# power.net
KiCad netlist of a schematic drawn in Altium Designer
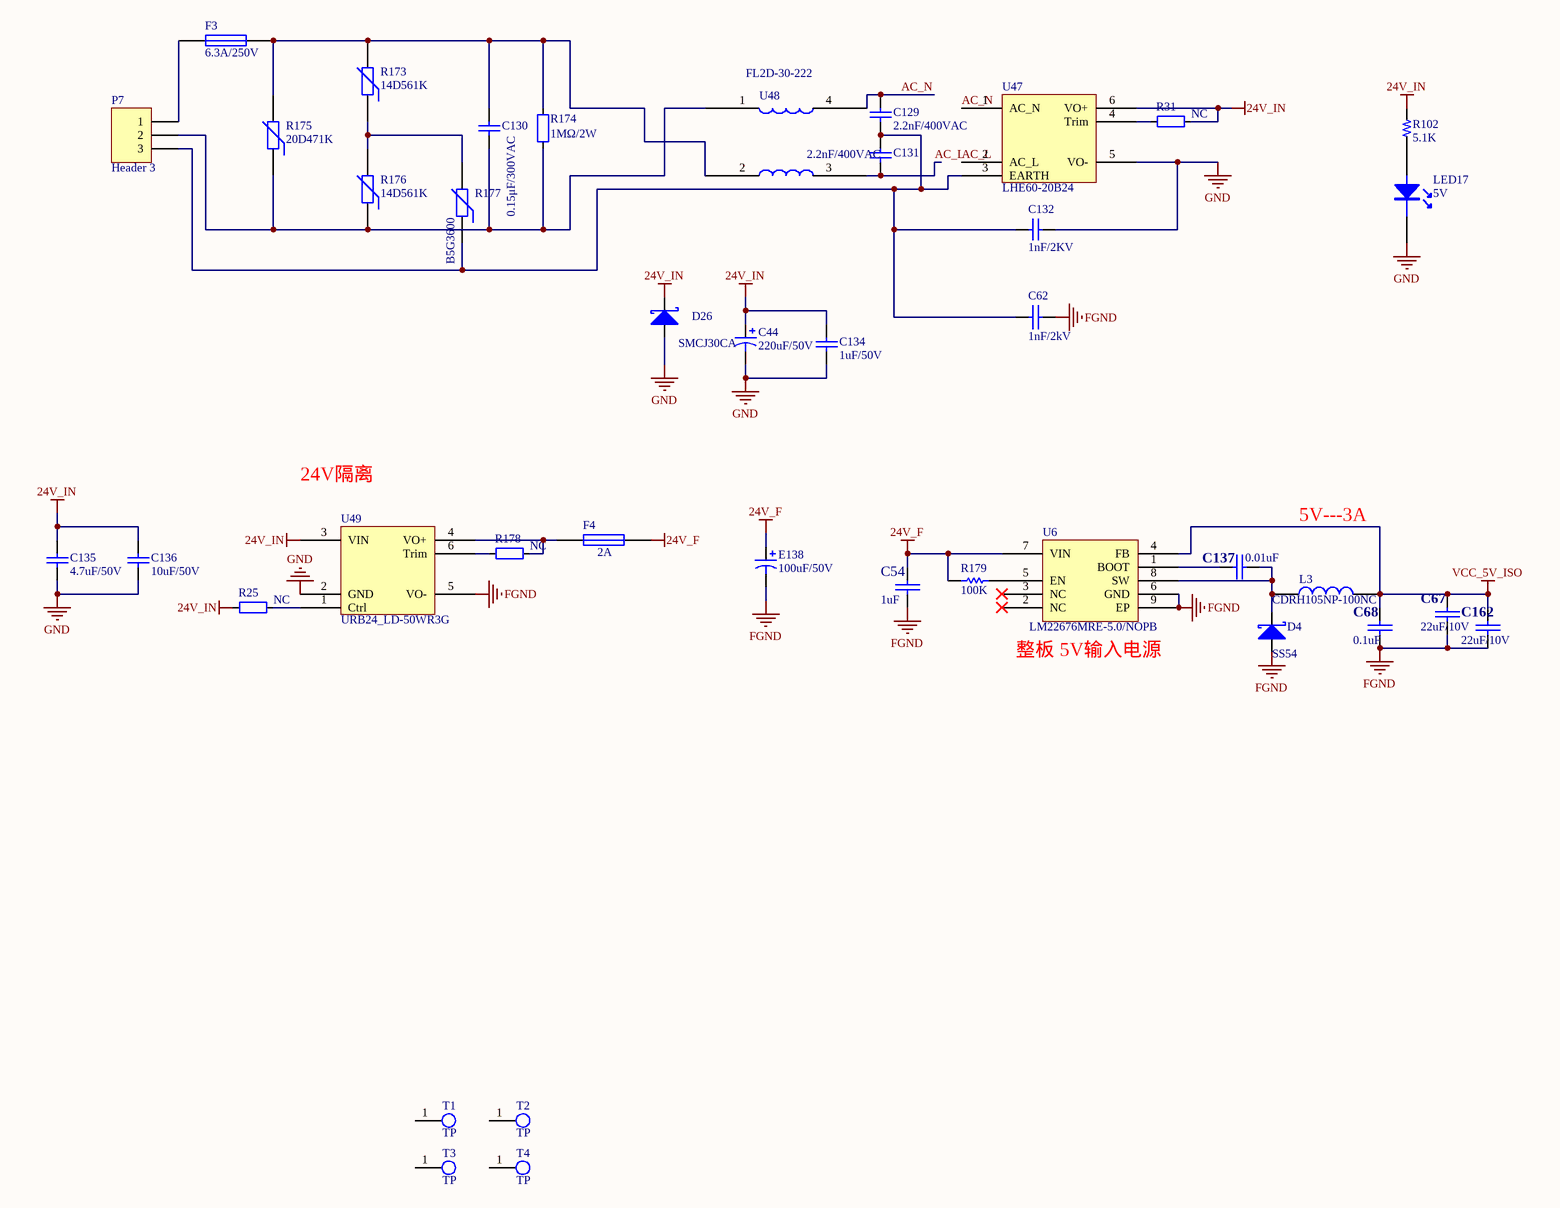
[diagram p0: power.SchDoc]

(export (version "E")
  (design (tool "Eeschema 10.0.6"))
  (components
    (comp (ref "C44")
      (value "220uF/50V")
      (footprint "Φ10×10")
      (description "Polarized Capacitor (Radial)")
      (fields (field (name "PUBLISHER") "Altium Limited"))
      (libsource (lib "Miscellaneous Devices") (part "Cap Pol1"))
    )
    (comp (ref "C54")
      (value "1uF")
      (footprint "0603C")
      (description "Capacitor")
      (libsource (lib "*") (part "CAP"))
    )
    (comp (ref "C62")
      (value "1nF/2kV")
      (footprint "1206C")
      (description "Capacitor")
      (libsource (lib "*") (part "CAP"))
    )
    (comp (ref "C67")
      (value "22uF/10V")
      (footprint "1210C")
      (description "Capacitor")
      (libsource (lib "*") (part "CAP"))
    )
    (comp (ref "C68")
      (value "0.1uF")
      (footprint "0603C")
      (description "Capacitor")
      (libsource (lib "*") (part "CAP"))
    )
    (comp (ref "C129")
      (value "2.2nF/400VAC")
      (footprint "15x18")
      (description "Capacitor")
      (fields (field (name "PUBLISHER") "Altium Limited"))
      (libsource (lib "Miscellaneous Devices") (part "Cap"))
    )
    (comp (ref "C130")
      (value "0.15μF/300VAC")
      (footprint "15x18")
      (description "Capacitor")
      (fields (field (name "PUBLISHER") "Altium Limited"))
      (libsource (lib "Miscellaneous Devices") (part "Cap"))
    )
    (comp (ref "C131")
      (value "2.2nF/400VAC")
      (footprint "15x18")
      (description "Capacitor")
      (fields (field (name "PUBLISHER") "Altium Limited"))
      (libsource (lib "Miscellaneous Devices") (part "Cap"))
    )
    (comp (ref "C132")
      (value "1nF/2KV")
      (footprint "1206C")
      (description "Capacitor")
      (fields (field (name "PUBLISHER") "Altium Limited"))
      (libsource (lib "Miscellaneous Devices") (part "Cap"))
    )
    (comp (ref "C134")
      (value "1uF/50V")
      (footprint "1210C")
      (description "Capacitor")
      (fields (field (name "PUBLISHER") "Altium Limited"))
      (libsource (lib "Miscellaneous Devices") (part "Cap"))
    )
    (comp (ref "C135")
      (value "4.7uF/50V")
      (footprint "1210C")
      (description "Capacitor")
      (fields (field (name "PUBLISHER") "Altium Limited"))
      (libsource (lib "Miscellaneous Devices") (part "Cap"))
    )
    (comp (ref "C136")
      (value "10uF/50V")
      (footprint "1210C")
      (description "Capacitor")
      (fields (field (name "PUBLISHER") "Altium Limited"))
      (libsource (lib "Miscellaneous Devices") (part "Cap"))
    )
    (comp (ref "C137")
      (value "0.01uF")
      (footprint "0603C")
      (description "Capacitor")
      (libsource (lib "*") (part "CAP"))
    )
    (comp (ref "C162")
      (value "22uF/10V")
      (footprint "1210C")
      (description "Capacitor")
      (libsource (lib "*") (part "CAP"))
    )
    (comp (ref "D4")
      (value "SS54")
      (footprint "SMC")
      (description "Schottky Diode")
      (libsource (lib "*") (part "DIODE S"))
    )
    (comp (ref "D26")
      (value "SMCJ30CA")
      (footprint "SMC")
      (description "Schottky Diode")
      (libsource (lib "*") (part "DIODE S"))
    )
    (comp (ref "E138")
      (value "100uF/50V")
      (footprint "Φ10×10")
      (description "Polarized Capacitor (Radial)")
      (fields (field (name "PUBLISHER") "Altium Limited"))
      (libsource (lib "Miscellaneous Devices") (part "Cap Pol1"))
    )
    (comp (ref "F3")
      (value "6.3A/250V")
      (footprint "可视开关电源保险丝座")
      (description "Fuse")
      (fields (field (name "PUBLISHER") "Altium Limited"))
      (libsource (lib "Miscellaneous Devices") (part "Fuse 1"))
    )
    (comp (ref "F4")
      (value "2A")
      (footprint "1812-F")
      (description "Fuse")
      (fields (field (name "PUBLISHER") "Altium Limited"))
      (libsource (lib "Miscellaneous Devices") (part "Fuse 1"))
    )
    (comp (ref "L3") (value "CDRH105NP-100NC") (footprint "CDRH105") (libsource (lib "*") (part "INDUCTOR")))
    (comp (ref "LED17") (value "5V") (footprint "0603LED") (libsource (lib "*") (part "LED")))
    (comp (ref "P7")
      (value "Header 3")
      (footprint "KF128V-3P")
      (description "Header, 3-Pin")
      (fields (field (name "PUBLISHER") "Altium Limited"))
      (libsource (lib "Miscellaneous Connectors") (part "Header 3"))
    )
    (comp (ref "R25") (value "NC") (footprint "0603r") (libsource (lib "RC_M_D_00") (part "RES0603")))
    (comp (ref "R31") (value "NC") (footprint "0603r") (libsource (lib "RC_M_D_00") (part "RES0603")))
    (comp (ref "R102")
      (value "5.1K")
      (footprint "0603R")
      (description "R")
      (libsource (lib "JRJ_1") (part "R"))
    )
    (comp (ref "R173")
      (value "14D561K")
      (footprint "14D561K")
      (description "Varistor (Voltage-Sensitive Resistor)")
      (fields (field (name "PUBLISHER") "Altium Limited"))
      (libsource (lib "Miscellaneous Devices") (part "Res Varistor"))
    )
    (comp (ref "R174") (value "1MΩ/2W") (footprint "5x15.5") (libsource (lib "RC_M_D_00") (part "RES0603")))
    (comp (ref "R175")
      (value "20D471K")
      (footprint "20D471K")
      (description "Varistor (Voltage-Sensitive Resistor)")
      (fields (field (name "PUBLISHER") "Altium Limited"))
      (libsource (lib "Miscellaneous Devices") (part "Res Varistor"))
    )
    (comp (ref "R176")
      (value "14D561K")
      (footprint "14D561K")
      (description "Varistor (Voltage-Sensitive Resistor)")
      (fields (field (name "PUBLISHER") "Altium Limited"))
      (libsource (lib "Miscellaneous Devices") (part "Res Varistor"))
    )
    (comp (ref "R177")
      (value "B5G3600")
      (footprint "B5G3600")
      (description "Varistor (Voltage-Sensitive Resistor)")
      (fields (field (name "PUBLISHER") "Altium Limited"))
      (libsource (lib "Miscellaneous Devices") (part "Res Varistor"))
    )
    (comp (ref "R178") (value "NC") (footprint "0603r") (libsource (lib "RC_M_D_00") (part "RES0603")))
    (comp (ref "R179")
      (value "100K")
      (footprint "0603R")
      (description "Resistor")
      (fields (field (name "PUBLISHER") "Altium Limited"))
      (libsource (lib "Miscellaneous Devices") (part "Res1"))
    )
    (comp (ref "T1") (value "TP") (footprint "m2.5") (libsource (lib "Schlib_20110825") (part "TP")))
    (comp (ref "T2") (value "TP") (footprint "m2.5") (libsource (lib "Schlib_20110825") (part "TP")))
    (comp (ref "T3") (value "TP") (footprint "m2.5") (libsource (lib "Schlib_20110825") (part "TP")))
    (comp (ref "T4") (value "TP") (footprint "m2.5") (libsource (lib "Schlib_20110825") (part "TP")))
    (comp (ref "U6")
      (value "LM22676MRE-5.0/NOPB")
      (footprint "SOP127P600X168_HS-8N")
      (libsource (lib "Schlib1") (part "LM22676MR-5.0"))
    )
    (comp (ref "U47")
      (value "LHE60-20B24")
      (footprint "LHE60-20B24")
      (libsource (lib "Schlib1") (part "LHE60-20B24"))
    )
    (comp (ref "U48")
      (value "FL2D-30-222")
      (footprint "TY-100P")
      (description "PCB mounting filters")
      (libsource (lib "power") (part "TY-100P"))
    )
    (comp (ref "U49")
      (value "URB24_LD-50WR3G")
      (footprint "URB24_LD-50WR3G")
      (libsource (lib "Schlib1") (part "URB24_LD-50WR3G"))
    )
  )
  (nets
    (net (code "1") (name "/AC_L") (class "Default")
      (node (ref "C131") (pin "1") (pinfunction "1_1") (pintype "passive"))
      (node (ref "U47") (pin "2") (pinfunction "AC_L_2") (pintype "passive"))
      (node (ref "U48") (pin "3") (pintype "passive"))
    )
    (net (code "2") (name "/AC_N") (class "Default")
      (node (ref "C129") (pin "2") (pinfunction "2_2") (pintype "passive"))
      (node (ref "U47") (pin "1") (pinfunction "AC_N_1") (pintype "passive"))
      (node (ref "U48") (pin "4") (pinfunction "L_4") (pintype "passive"))
    )
    (net (code "3") (name "24V_F") (class "Default")
      (node (ref "C54") (pin "2") (pinfunction "2_2") (pintype "passive"))
      (node (ref "E138") (pin "1") (pinfunction "1_1") (pintype "passive"))
      (node (ref "F4") (pin "2") (pinfunction "2_2") (pintype "passive"))
      (node (ref "R179") (pin "2") (pinfunction "2_2") (pintype "passive"))
      (node (ref "U6") (pin "7") (pinfunction "VIN_7") (pintype "passive"))
    )
    (net (code "4") (name "24V_IN") (class "Default")
      (node (ref "C134") (pin "2") (pinfunction "2_2") (pintype "passive"))
      (node (ref "C135") (pin "2") (pinfunction "2_2") (pintype "passive"))
      (node (ref "C136") (pin "2") (pinfunction "2_2") (pintype "passive"))
      (node (ref "C44") (pin "1") (pinfunction "1_1") (pintype "passive"))
      (node (ref "D26") (pin "2") (pinfunction "K_2") (pintype "passive"))
      (node (ref "R102") (pin "2") (pintype "passive"))
      (node (ref "R25") (pin "1") (pinfunction "1_1") (pintype "passive"))
      (node (ref "R31") (pin "2") (pinfunction "2_2") (pintype "passive"))
      (node (ref "U47") (pin "6") (pinfunction "VO+_6") (pintype "passive"))
      (node (ref "U49") (pin "3") (pinfunction "VIN_3") (pintype "passive"))
    )
    (net (code "5") (name "FGND") (class "Default")
      (node (ref "C162") (pin "2") (pinfunction "2_2") (pintype "passive"))
      (node (ref "C54") (pin "1") (pinfunction "1_1") (pintype "passive"))
      (node (ref "C62") (pin "1") (pinfunction "1_1") (pintype "passive"))
      (node (ref "C67") (pin "2") (pinfunction "2_2") (pintype "passive"))
      (node (ref "C68") (pin "2") (pinfunction "2_2") (pintype "passive"))
      (node (ref "D4") (pin "1") (pinfunction "A_1") (pintype "passive"))
      (node (ref "E138") (pin "2") (pinfunction "2_2") (pintype "passive"))
      (node (ref "U49") (pin "5") (pinfunction "VO-_5") (pintype "passive"))
      (node (ref "U6") (pin "6") (pinfunction "GND_6") (pintype "passive"))
      (node (ref "U6") (pin "9") (pinfunction "EP_9") (pintype "passive"))
    )
    (net (code "6") (name "GND") (class "Default")
      (node (ref "C132") (pin "1") (pinfunction "1_1") (pintype "passive"))
      (node (ref "C134") (pin "1") (pinfunction "1_1") (pintype "passive"))
      (node (ref "C135") (pin "1") (pinfunction "1_1") (pintype "passive"))
      (node (ref "C136") (pin "1") (pinfunction "1_1") (pintype "passive"))
      (node (ref "C44") (pin "2") (pinfunction "2_2") (pintype "passive"))
      (node (ref "D26") (pin "1") (pinfunction "A_1") (pintype "passive"))
      (node (ref "LED17") (pin "2") (pinfunction "2_2") (pintype "passive"))
      (node (ref "U47") (pin "5") (pinfunction "VO-_5") (pintype "passive"))
      (node (ref "U49") (pin "2") (pinfunction "GND_2") (pintype "passive"))
    )
    (net (code "7") (name "Net-(C130-Pad1)") (class "Default")
      (node (ref "C130") (pin "1") (pinfunction "1_1") (pintype "passive"))
      (node (ref "P7") (pin "2") (pinfunction "2_2") (pintype "passive"))
      (node (ref "R174") (pin "2") (pinfunction "2_2") (pintype "passive"))
      (node (ref "R175") (pin "1") (pinfunction "1_1") (pintype "passive"))
      (node (ref "R176") (pin "1") (pinfunction "1_1") (pintype "passive"))
      (node (ref "U48") (pin "1") (pinfunction "L_1") (pintype "passive"))
    )
    (net (code "8") (name "Net-(C130-Pad2)") (class "Default")
      (node (ref "C130") (pin "2") (pinfunction "2_2") (pintype "passive"))
      (node (ref "F3") (pin "2") (pinfunction "2_2") (pintype "passive"))
      (node (ref "R173") (pin "2") (pinfunction "2_2") (pintype "passive"))
      (node (ref "R174") (pin "1") (pinfunction "1_1") (pintype "passive"))
      (node (ref "R175") (pin "2") (pinfunction "2_2") (pintype "passive"))
      (node (ref "U48") (pin "2") (pinfunction "L_2") (pintype "passive"))
    )
    (net (code "9") (name "Net-(D4-K)") (class "Default")
      (node (ref "C137") (pin "1") (pinfunction "1_1") (pintype "passive"))
      (node (ref "D4") (pin "2") (pinfunction "K_2") (pintype "passive"))
      (node (ref "L3") (pin "1") (pinfunction "1_1") (pintype "passive"))
      (node (ref "U6") (pin "8") (pinfunction "SW_8") (pintype "passive"))
    )
    (net (code "10") (name "Net-(F3-Pad1)") (class "Default")
      (node (ref "F3") (pin "1") (pinfunction "1_1") (pintype "passive"))
      (node (ref "P7") (pin "1") (pinfunction "1_1") (pintype "passive"))
    )
    (net (code "11") (name "Net-(LED17-Pad1)") (class "Default")
      (node (ref "LED17") (pin "1") (pinfunction "1_1") (pintype "passive"))
      (node (ref "R102") (pin "1") (pintype "passive"))
    )
    (net (code "12") (name "Net-(R173-Pad1)") (class "Default")
      (node (ref "R173") (pin "1") (pinfunction "1_1") (pintype "passive"))
      (node (ref "R176") (pin "2") (pinfunction "2_2") (pintype "passive"))
      (node (ref "R177") (pin "2") (pinfunction "2_2") (pintype "passive"))
    )
    (net (code "13") (name "Net-(U6-BOOT)") (class "Default")
      (node (ref "C137") (pin "2") (pinfunction "2_2") (pintype "passive"))
      (node (ref "U6") (pin "1") (pinfunction "BOOT_1") (pintype "passive"))
    )
    (net (code "14") (name "Net-(U6-EN)") (class "Default")
      (node (ref "R179") (pin "1") (pinfunction "1_1") (pintype "passive"))
      (node (ref "U6") (pin "5") (pinfunction "EN_5") (pintype "passive"))
    )
    (net (code "15") (name "Net-(U47-EARTH)") (class "Default")
      (node (ref "C129") (pin "1") (pinfunction "1_1") (pintype "passive"))
      (node (ref "C131") (pin "2") (pinfunction "2_2") (pintype "passive"))
      (node (ref "C132") (pin "2") (pinfunction "2_2") (pintype "passive"))
      (node (ref "C62") (pin "2") (pinfunction "2_2") (pintype "passive"))
      (node (ref "P7") (pin "3") (pinfunction "3_3") (pintype "passive"))
      (node (ref "R177") (pin "1") (pinfunction "1_1") (pintype "passive"))
      (node (ref "U47") (pin "3") (pinfunction "EARTH_3") (pintype "passive"))
    )
    (net (code "16") (name "Net-(U47-Trim)") (class "Default")
      (node (ref "R31") (pin "1") (pinfunction "1_1") (pintype "passive"))
      (node (ref "U47") (pin "4") (pinfunction "Trim_4") (pintype "passive"))
    )
    (net (code "17") (name "Net-(U49-Ctrl)") (class "Default")
      (node (ref "R25") (pin "2") (pinfunction "2_2") (pintype "passive"))
      (node (ref "U49") (pin "1") (pinfunction "Ctrl_1") (pintype "passive"))
    )
    (net (code "18") (name "Net-(U49-Trim)") (class "Default")
      (node (ref "R178") (pin "1") (pinfunction "1_1") (pintype "passive"))
      (node (ref "U49") (pin "6") (pinfunction "Trim_6") (pintype "passive"))
    )
    (net (code "19") (name "Net-(U49-VO+)") (class "Default")
      (node (ref "F4") (pin "1") (pinfunction "1_1") (pintype "passive"))
      (node (ref "R178") (pin "2") (pinfunction "2_2") (pintype "passive"))
      (node (ref "U49") (pin "4") (pinfunction "VO+_4") (pintype "passive"))
    )
    (net (code "20") (name "VCC_5V_ISO") (class "Default")
      (node (ref "C162") (pin "1") (pinfunction "1_1") (pintype "passive"))
      (node (ref "C67") (pin "1") (pinfunction "1_1") (pintype "passive"))
      (node (ref "C68") (pin "1") (pinfunction "1_1") (pintype "passive"))
      (node (ref "L3") (pin "2") (pinfunction "2_2") (pintype "passive"))
      (node (ref "U6") (pin "4") (pinfunction "FB_4") (pintype "passive"))
    )
    (net (code "21") (name "unconnected-(T1-Pad1)") (class "Default")
      (node (ref "T1") (pin "1") (pintype "passive"))
    )
    (net (code "22") (name "unconnected-(T2-Pad1)") (class "Default")
      (node (ref "T2") (pin "1") (pintype "passive"))
    )
    (net (code "23") (name "unconnected-(T3-Pad1)") (class "Default")
      (node (ref "T3") (pin "1") (pintype "passive"))
    )
    (net (code "24") (name "unconnected-(T4-Pad1)") (class "Default")
      (node (ref "T4") (pin "1") (pintype "passive"))
    )
    (net (code "25") (name "unconnected-(U6-NC-Pad2)") (class "Default")
      (node (ref "U6") (pin "2") (pinfunction "NC_2") (pintype "passive+no_connect"))
    )
    (net (code "26") (name "unconnected-(U6-NC-Pad3)") (class "Default")
      (node (ref "U6") (pin "3") (pinfunction "NC_3") (pintype "passive+no_connect"))
    )
  )
)
